# pc_ads1292r_shield_v2.net
KiCad netlist of a schematic drawn in EAGLE
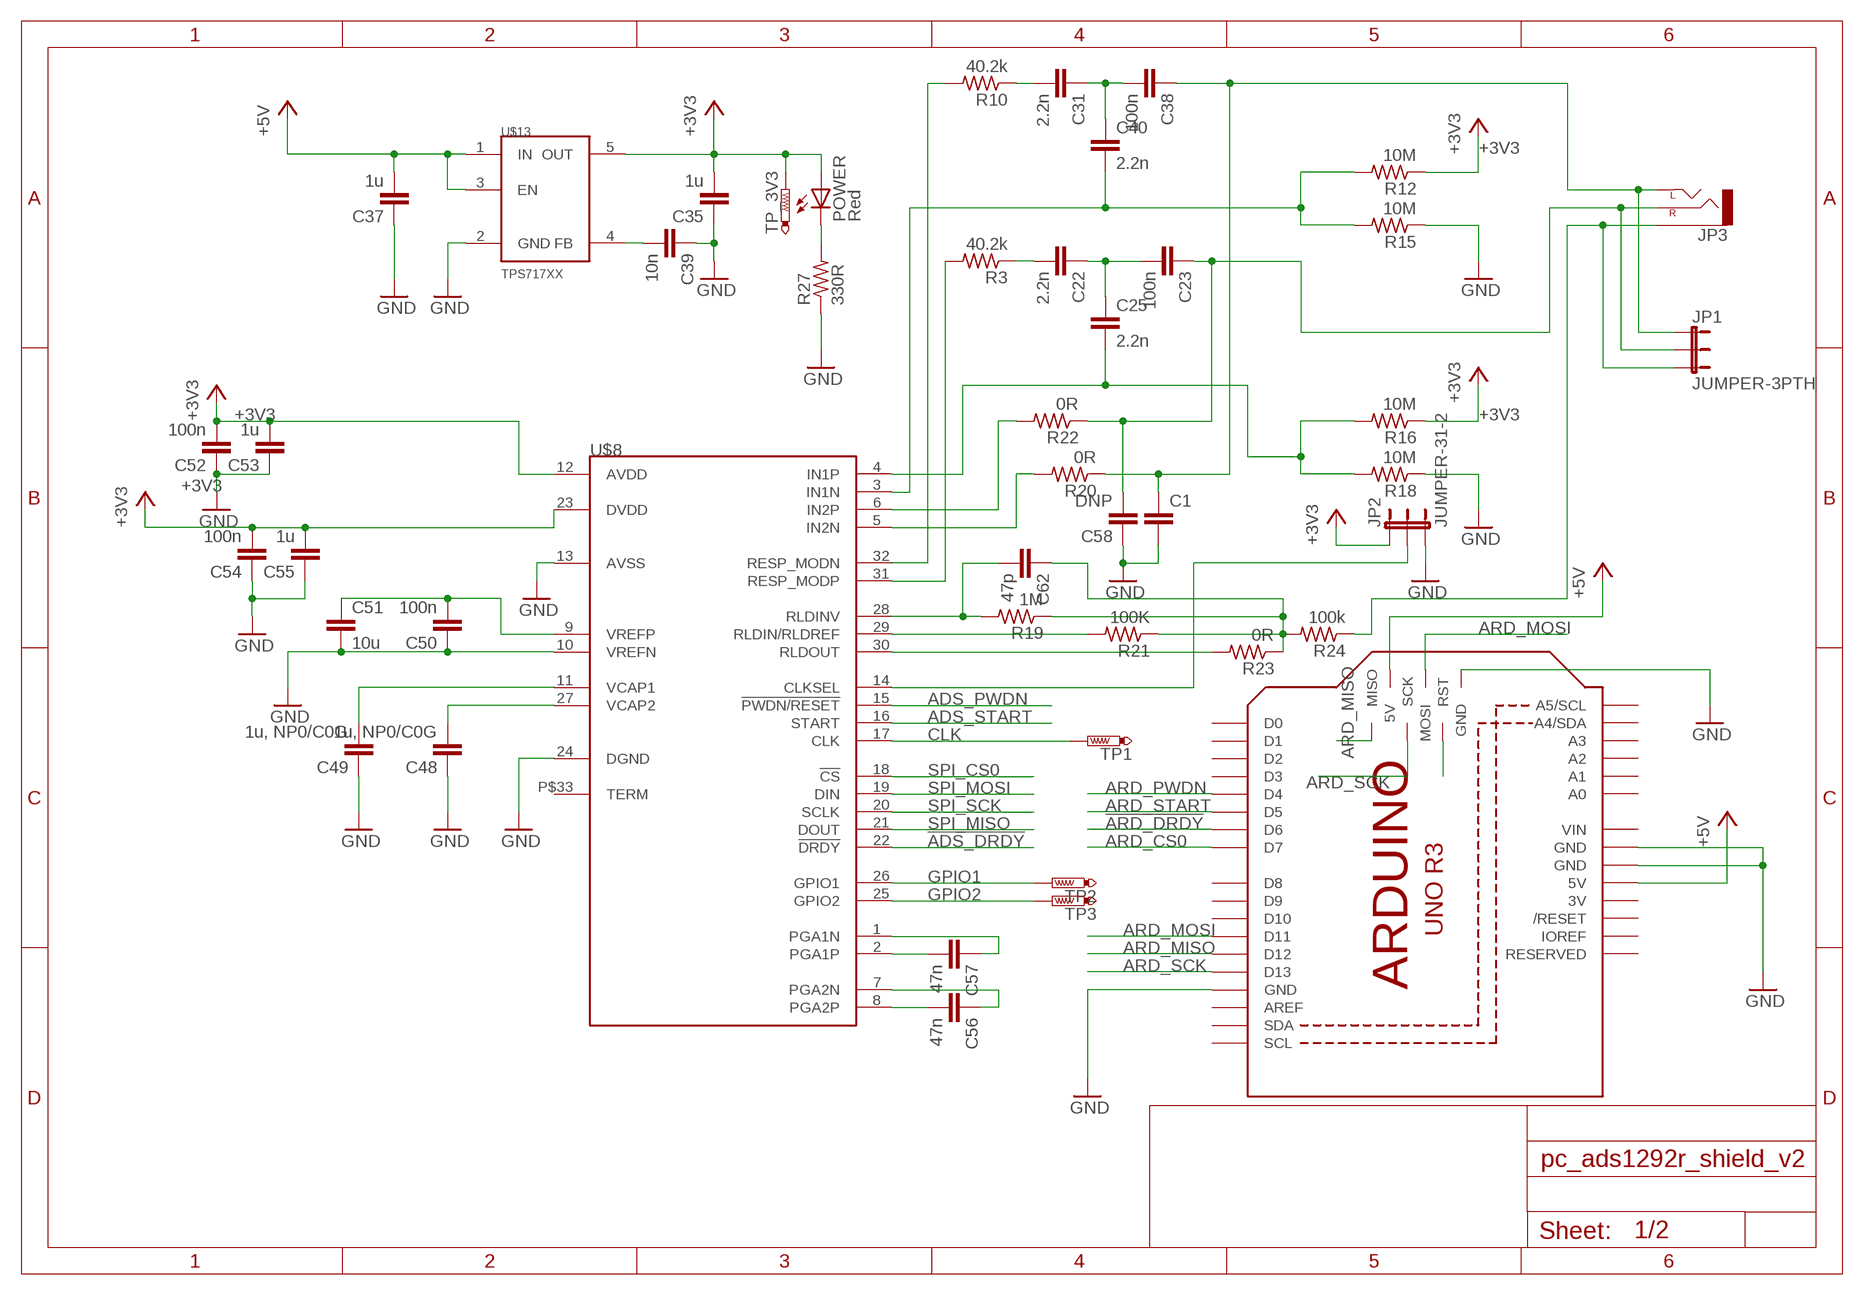
[diagram p0: schematic, sheet 1]
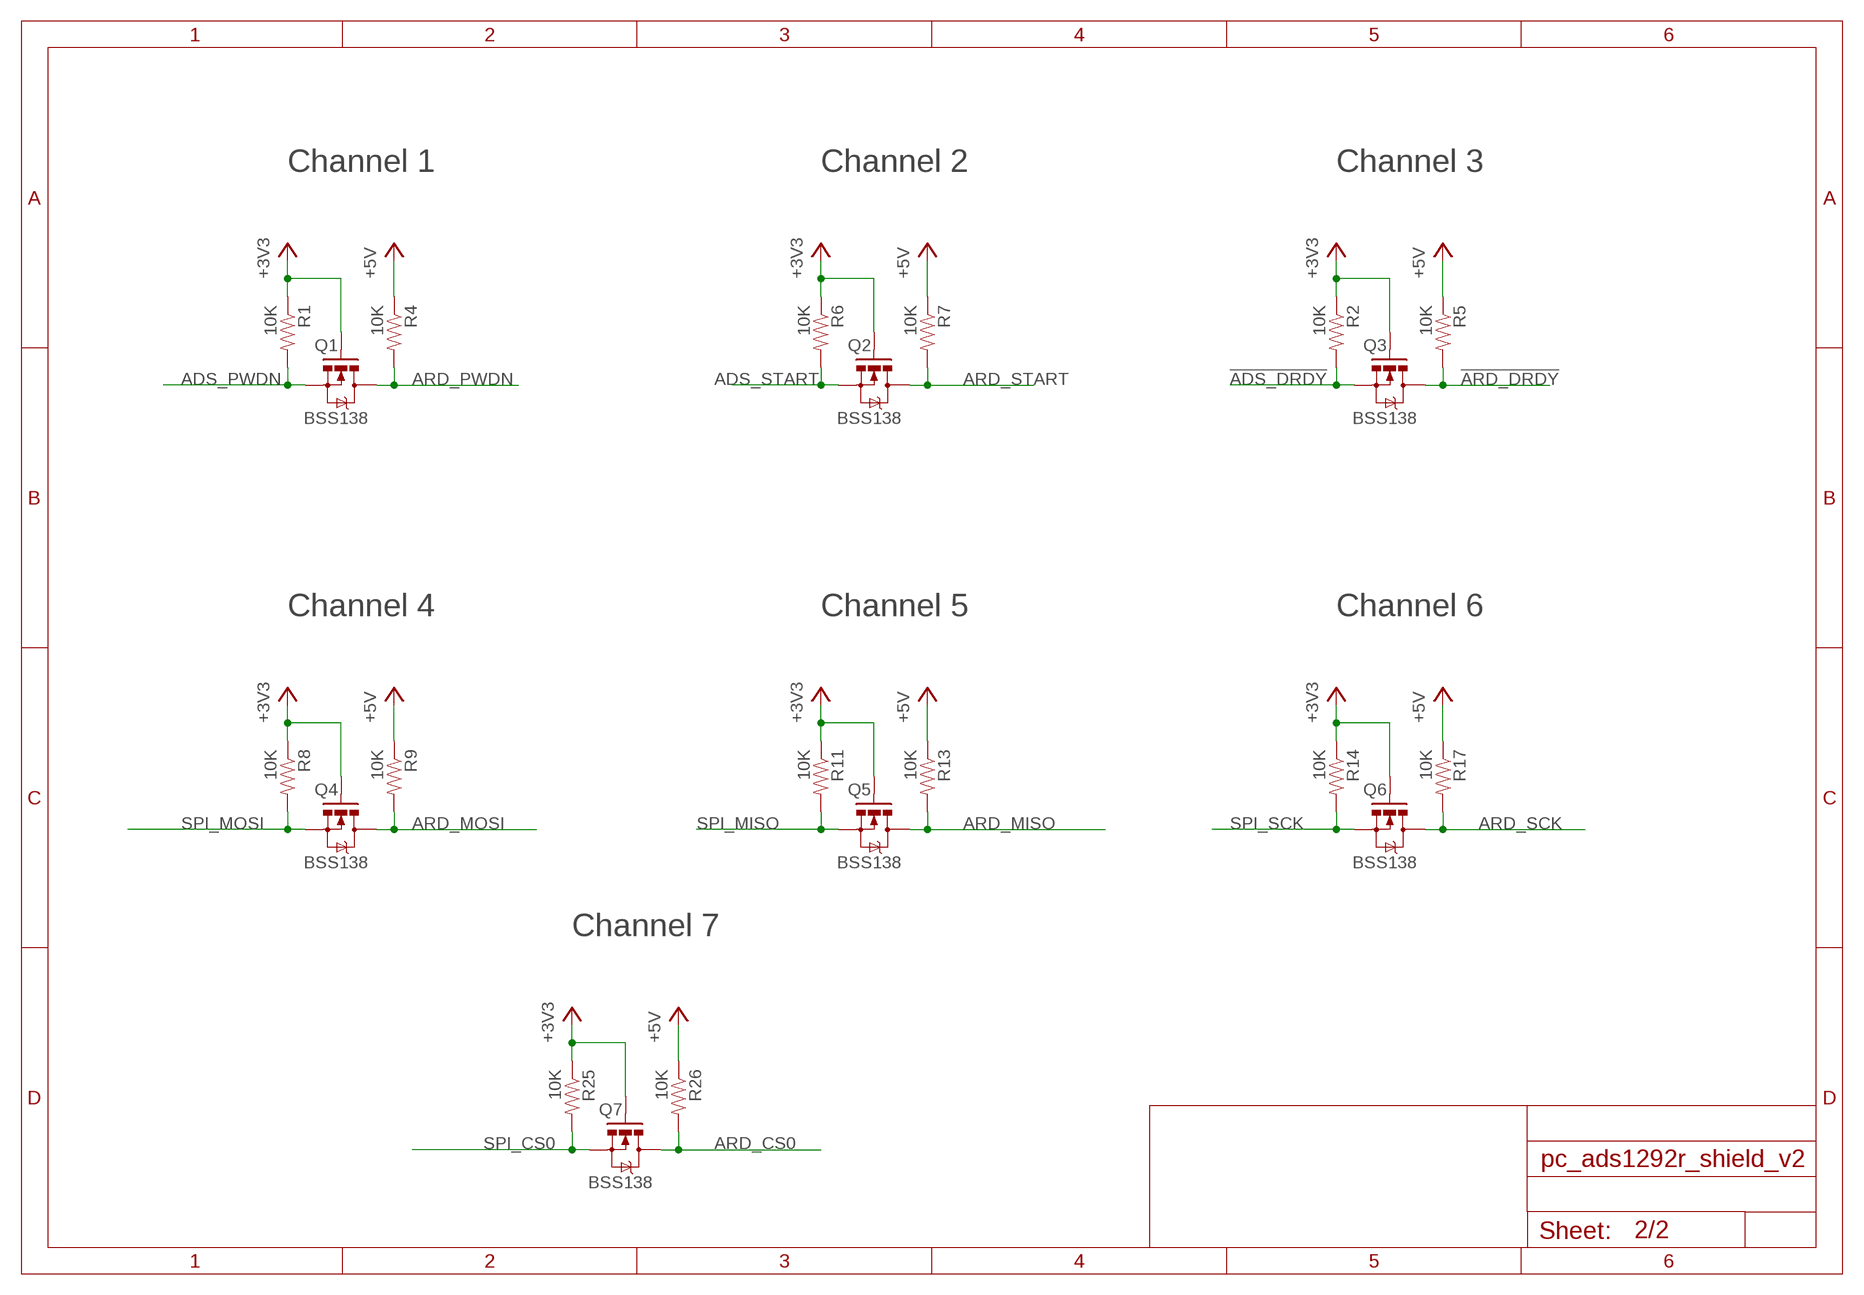
[diagram p1: schematic, sheet 2]

(export (version "E")
  (design (tool "Eeschema 10.0.6"))
  (components
    (comp (ref "C1")
      (value "C-EUC0402")
      (footprint "eagle-import:C0402")
      (libsource (lib "eagle-import") (part "C-EUC0402"))
    )
    (comp (ref "C22")
      (value "2.2n")
      (footprint "eagle-import:C0402")
      (libsource (lib "eagle-import") (part "C-EUC0402"))
    )
    (comp (ref "C23")
      (value "100n")
      (footprint "eagle-import:C0402")
      (libsource (lib "eagle-import") (part "C-EUC0402"))
    )
    (comp (ref "C25")
      (value "2.2n")
      (footprint "eagle-import:C0402")
      (libsource (lib "eagle-import") (part "C-EUC0402"))
    )
    (comp (ref "C31")
      (value "2.2n")
      (footprint "eagle-import:C0402")
      (libsource (lib "eagle-import") (part "C-EUC0402"))
    )
    (comp (ref "C35")
      (value "1u")
      (footprint "eagle-import:C0402")
      (libsource (lib "eagle-import") (part "C-EUC0402"))
    )
    (comp (ref "C37")
      (value "1u")
      (footprint "eagle-import:C0402")
      (libsource (lib "eagle-import") (part "C-EUC0402"))
    )
    (comp (ref "C38")
      (value "100n")
      (footprint "eagle-import:C0402")
      (libsource (lib "eagle-import") (part "C-EUC0402"))
    )
    (comp (ref "C39")
      (value "10n")
      (footprint "eagle-import:C0402")
      (libsource (lib "eagle-import") (part "C-EUC0402"))
    )
    (comp (ref "C40")
      (value "2.2n")
      (footprint "eagle-import:C0402")
      (libsource (lib "eagle-import") (part "C-EUC0402"))
    )
    (comp (ref "C48")
      (value "1u, NP0/C0G")
      (footprint "eagle-import:C0402")
      (libsource (lib "eagle-import") (part "C-EUC0402"))
    )
    (comp (ref "C49")
      (value "1u, NP0/C0G")
      (footprint "eagle-import:C0402")
      (libsource (lib "eagle-import") (part "C-EUC0402"))
    )
    (comp (ref "C50")
      (value "100n")
      (footprint "eagle-import:C0402")
      (libsource (lib "eagle-import") (part "C-EUC0402"))
    )
    (comp (ref "C51")
      (value "10u")
      (footprint "eagle-import:C0603")
      (libsource (lib "eagle-import") (part "resistor_C-EUC0603"))
    )
    (comp (ref "C52")
      (value "100n")
      (footprint "eagle-import:C0402")
      (libsource (lib "eagle-import") (part "C-EUC0402"))
    )
    (comp (ref "C53")
      (value "1u")
      (footprint "eagle-import:C0402")
      (libsource (lib "eagle-import") (part "C-EUC0402"))
    )
    (comp (ref "C54")
      (value "100n")
      (footprint "eagle-import:C0402")
      (libsource (lib "eagle-import") (part "C-EUC0402"))
    )
    (comp (ref "C55")
      (value "1u")
      (footprint "eagle-import:C0402")
      (libsource (lib "eagle-import") (part "C-EUC0402"))
    )
    (comp (ref "C56")
      (value "47n")
      (footprint "eagle-import:C0402")
      (libsource (lib "eagle-import") (part "C-EUC0402"))
    )
    (comp (ref "C57")
      (value "47n")
      (footprint "eagle-import:C0402")
      (libsource (lib "eagle-import") (part "C-EUC0402"))
    )
    (comp (ref "C58")
      (value "DNP")
      (footprint "eagle-import:C0402")
      (libsource (lib "eagle-import") (part "C-EUC0402"))
    )
    (comp (ref "C62")
      (value "47p")
      (footprint "eagle-import:C0402")
      (libsource (lib "eagle-import") (part "C-EUC0402"))
    )
    (comp (ref "JP1")
      (value "JUMPER-3PTH")
      (footprint "eagle-import:1X03")
      (libsource (lib "eagle-import") (part "JUMPER-3PTH"))
    )
    (comp (ref "JP2")
      (value "JUMPER-31-2")
      (footprint "eagle-import:SJ_3_PASTE1&2")
      (libsource (lib "eagle-import") (part "JUMPER-31-2"))
    )
    (comp (ref "JP3")
      (value "AUDIO-JACKSMD2")
      (footprint "eagle-import:AUDIO-JACK-3.5MM-SMD")
      (libsource (lib "eagle-import") (part "AUDIO-JACKSMD2"))
    )
    (comp (ref "M1")
      (value "ARDUINO_R3_ICSP")
      (footprint "eagle-import:ARDUINOR3_ICSP")
      (libsource (lib "eagle-import") (part "ARDUINO_R3_ICSP"))
    )
    (comp (ref "POWER")
      (value "Red")
      (footprint "eagle-import:CHIPLED_0603")
      (libsource (lib "eagle-import") (part "LEDCHIPLED_0603"))
    )
    (comp (ref "R3")
      (value "40.2k")
      (footprint "eagle-import:R0402")
      (libsource (lib "eagle-import") (part "R-US_R0402"))
    )
    (comp (ref "R10")
      (value "40.2k")
      (footprint "eagle-import:R0402")
      (libsource (lib "eagle-import") (part "R-US_R0402"))
    )
    (comp (ref "R12")
      (value "10M")
      (footprint "eagle-import:R0402")
      (libsource (lib "eagle-import") (part "R-US_R0402"))
    )
    (comp (ref "R15")
      (value "10M")
      (footprint "eagle-import:R0402")
      (libsource (lib "eagle-import") (part "R-US_R0402"))
    )
    (comp (ref "R16")
      (value "10M")
      (footprint "eagle-import:R0402")
      (libsource (lib "eagle-import") (part "R-US_R0402"))
    )
    (comp (ref "R18")
      (value "10M")
      (footprint "eagle-import:R0402")
      (libsource (lib "eagle-import") (part "R-US_R0402"))
    )
    (comp (ref "R19")
      (value "1M")
      (footprint "eagle-import:R0402")
      (libsource (lib "eagle-import") (part "R-US_R0402"))
    )
    (comp (ref "R20")
      (value "0R")
      (footprint "eagle-import:R0402")
      (libsource (lib "eagle-import") (part "R-US_R0402"))
    )
    (comp (ref "R21")
      (value "100K")
      (footprint "eagle-import:R0402")
      (libsource (lib "eagle-import") (part "R-US_R0402"))
    )
    (comp (ref "R22")
      (value "0R")
      (footprint "eagle-import:R0402")
      (libsource (lib "eagle-import") (part "R-US_R0402"))
    )
    (comp (ref "R23")
      (value "0R")
      (footprint "eagle-import:R0402")
      (libsource (lib "eagle-import") (part "R-US_R0402"))
    )
    (comp (ref "R24")
      (value "100k")
      (footprint "eagle-import:R0402")
      (libsource (lib "eagle-import") (part "R-US_R0402"))
    )
    (comp (ref "R27")
      (value "330R")
      (footprint "eagle-import:R0402")
      (libsource (lib "eagle-import") (part "R-US_R0402"))
    )
    (comp (ref "TP1")
      (value "PTR1PAD1-17")
      (footprint "eagle-import:P1-17")
      (libsource (lib "eagle-import") (part "PTR1PAD1-17"))
    )
    (comp (ref "TP2")
      (value "PTR1PAD1-17")
      (footprint "eagle-import:P1-17")
      (libsource (lib "eagle-import") (part "PTR1PAD1-17"))
    )
    (comp (ref "TP3")
      (value "PTR1PAD1-17")
      (footprint "eagle-import:P1-17")
      (libsource (lib "eagle-import") (part "PTR1PAD1-17"))
    )
    (comp (ref "TP_3V3")
      (value "PTR1PAD1-13")
      (footprint "eagle-import:P1-13")
      (libsource (lib "eagle-import") (part "PTR1PAD1-13"))
    )
    (comp (ref "U$8")
      (value "ADS1292RPVQFN32")
      (footprint "eagle-import:S-PVQFN-N32")
      (libsource (lib "eagle-import") (part "ADS1292RPVQFN32"))
    )
    (comp (ref "U$13")
      (value "TPS717XX")
      (footprint "eagle-import:SC70-5")
      (libsource (lib "eagle-import") (part "TPS717XX"))
    )
    (comp (ref "Q1")
      (value "BSS138")
      (footprint "eagle-import:SOT23-3")
      (libsource (lib "eagle-import") (part "MOSFET-NCHANNELSMD"))
    )
    (comp (ref "Q2")
      (value "BSS138")
      (footprint "eagle-import:SOT23-3")
      (libsource (lib "eagle-import") (part "MOSFET-NCHANNELSMD"))
    )
    (comp (ref "Q3")
      (value "BSS138")
      (footprint "eagle-import:SOT23-3")
      (libsource (lib "eagle-import") (part "MOSFET-NCHANNELSMD"))
    )
    (comp (ref "Q4")
      (value "BSS138")
      (footprint "eagle-import:SOT23-3")
      (libsource (lib "eagle-import") (part "MOSFET-NCHANNELSMD"))
    )
    (comp (ref "Q5")
      (value "BSS138")
      (footprint "eagle-import:SOT23-3")
      (libsource (lib "eagle-import") (part "MOSFET-NCHANNELSMD"))
    )
    (comp (ref "Q6")
      (value "BSS138")
      (footprint "eagle-import:SOT23-3")
      (libsource (lib "eagle-import") (part "MOSFET-NCHANNELSMD"))
    )
    (comp (ref "Q7")
      (value "BSS138")
      (footprint "eagle-import:SOT23-3")
      (libsource (lib "eagle-import") (part "MOSFET-NCHANNELSMD"))
    )
    (comp (ref "R1")
      (value "10K")
      (footprint "eagle-import:0603-RES")
      (libsource (lib "eagle-import") (part "RESISTOR0603-RES"))
    )
    (comp (ref "R2")
      (value "10K")
      (footprint "eagle-import:0603-RES")
      (libsource (lib "eagle-import") (part "RESISTOR0603-RES"))
    )
    (comp (ref "R4")
      (value "10K")
      (footprint "eagle-import:0603-RES")
      (libsource (lib "eagle-import") (part "RESISTOR0603-RES"))
    )
    (comp (ref "R5")
      (value "10K")
      (footprint "eagle-import:0603-RES")
      (libsource (lib "eagle-import") (part "RESISTOR0603-RES"))
    )
    (comp (ref "R6")
      (value "10K")
      (footprint "eagle-import:0603-RES")
      (libsource (lib "eagle-import") (part "RESISTOR0603-RES"))
    )
    (comp (ref "R7")
      (value "10K")
      (footprint "eagle-import:0603-RES")
      (libsource (lib "eagle-import") (part "RESISTOR0603-RES"))
    )
    (comp (ref "R8")
      (value "10K")
      (footprint "eagle-import:0603-RES")
      (libsource (lib "eagle-import") (part "RESISTOR0603-RES"))
    )
    (comp (ref "R9")
      (value "10K")
      (footprint "eagle-import:0603-RES")
      (libsource (lib "eagle-import") (part "RESISTOR0603-RES"))
    )
    (comp (ref "R11")
      (value "10K")
      (footprint "eagle-import:0603-RES")
      (libsource (lib "eagle-import") (part "RESISTOR0603-RES"))
    )
    (comp (ref "R13")
      (value "10K")
      (footprint "eagle-import:0603-RES")
      (libsource (lib "eagle-import") (part "RESISTOR0603-RES"))
    )
    (comp (ref "R14")
      (value "10K")
      (footprint "eagle-import:0603-RES")
      (libsource (lib "eagle-import") (part "RESISTOR0603-RES"))
    )
    (comp (ref "R17")
      (value "10K")
      (footprint "eagle-import:0603-RES")
      (libsource (lib "eagle-import") (part "RESISTOR0603-RES"))
    )
    (comp (ref "R25")
      (value "10K")
      (footprint "eagle-import:0603-RES")
      (libsource (lib "eagle-import") (part "RESISTOR0603-RES"))
    )
    (comp (ref "R26")
      (value "10K")
      (footprint "eagle-import:0603-RES")
      (libsource (lib "eagle-import") (part "RESISTOR0603-RES"))
    )
  )
  (nets
    (net (code "1") (name "+3V3") (class "Default")
      (node (ref "C35") (pin "2") (pinfunction "2_2") (pintype "passive"))
      (node (ref "C52") (pin "2") (pinfunction "2_2") (pintype "passive"))
      (node (ref "C53") (pin "2") (pinfunction "2_2") (pintype "passive"))
      (node (ref "C54") (pin "2") (pinfunction "2_2") (pintype "passive"))
      (node (ref "C55") (pin "2") (pinfunction "2_2") (pintype "passive"))
      (node (ref "JP2") (pin "1") (pinfunction "1_1") (pintype "passive"))
      (node (ref "POWER") (pin "A") (pinfunction "A_A") (pintype "passive"))
      (node (ref "Q1") (pin "1") (pinfunction "G_1") (pintype "passive"))
      (node (ref "Q2") (pin "1") (pinfunction "G_1") (pintype "passive"))
      (node (ref "Q3") (pin "1") (pinfunction "G_1") (pintype "passive"))
      (node (ref "Q4") (pin "1") (pinfunction "G_1") (pintype "passive"))
      (node (ref "Q5") (pin "1") (pinfunction "G_1") (pintype "passive"))
      (node (ref "Q6") (pin "1") (pinfunction "G_1") (pintype "passive"))
      (node (ref "Q7") (pin "1") (pinfunction "G_1") (pintype "passive"))
      (node (ref "R1") (pin "1") (pinfunction "1_1") (pintype "passive"))
      (node (ref "R11") (pin "1") (pinfunction "1_1") (pintype "passive"))
      (node (ref "R12") (pin "1") (pinfunction "1_1") (pintype "passive"))
      (node (ref "R14") (pin "1") (pinfunction "1_1") (pintype "passive"))
      (node (ref "R16") (pin "1") (pinfunction "1_1") (pintype "passive"))
      (node (ref "R2") (pin "1") (pinfunction "1_1") (pintype "passive"))
      (node (ref "R25") (pin "1") (pinfunction "1_1") (pintype "passive"))
      (node (ref "R6") (pin "1") (pinfunction "1_1") (pintype "passive"))
      (node (ref "R8") (pin "1") (pinfunction "1_1") (pintype "passive"))
      (node (ref "TP_3V3") (pin "TP") (pinfunction "TP_TP") (pintype "input"))
      (node (ref "U$13") (pin "5") (pinfunction "OUT_5") (pintype "bidirectional"))
      (node (ref "U$8") (pin "12") (pinfunction "AVDD_12") (pintype "power_in"))
      (node (ref "U$8") (pin "23") (pinfunction "DVDD_23") (pintype "power_in"))
    )
    (net (code "2") (name "+5V") (class "Default")
      (node (ref "C37") (pin "2") (pinfunction "2_2") (pintype "passive"))
      (node (ref "M1") (pin "5V") (pinfunction "5V_5V") (pintype "power_in"))
      (node (ref "M1") (pin "5V_ICSP") (pinfunction "5V_5V_ICSP") (pintype "passive"))
      (node (ref "R13") (pin "1") (pinfunction "1_1") (pintype "passive"))
      (node (ref "R17") (pin "1") (pinfunction "1_1") (pintype "passive"))
      (node (ref "R26") (pin "1") (pinfunction "1_1") (pintype "passive"))
      (node (ref "R4") (pin "1") (pinfunction "1_1") (pintype "passive"))
      (node (ref "R5") (pin "1") (pinfunction "1_1") (pintype "passive"))
      (node (ref "R7") (pin "1") (pinfunction "1_1") (pintype "passive"))
      (node (ref "R9") (pin "1") (pinfunction "1_1") (pintype "passive"))
      (node (ref "U$13") (pin "1") (pinfunction "IN_1") (pintype "bidirectional"))
      (node (ref "U$13") (pin "3") (pinfunction "EN_3") (pintype "bidirectional"))
    )
    (net (code "3") (name "3V") (class "Default")
      (node (ref "M1") (pin "3V") (pinfunction "3V_3V") (pintype "power_in"))
    )
    (net (code "4") (name "ADS_PWDN") (class "Default")
      (node (ref "Q1") (pin "2") (pinfunction "S_2") (pintype "passive"))
      (node (ref "R1") (pin "2") (pinfunction "2_2") (pintype "passive"))
      (node (ref "U$8") (pin "15") (pinfunction "~{PWDN/RESET}_15") (pintype "bidirectional"))
    )
    (net (code "5") (name "ADS_START") (class "Default")
      (node (ref "Q2") (pin "2") (pinfunction "S_2") (pintype "passive"))
      (node (ref "R6") (pin "2") (pinfunction "2_2") (pintype "passive"))
      (node (ref "U$8") (pin "16") (pinfunction "START_16") (pintype "bidirectional"))
    )
    (net (code "6") (name "ARD_CS0") (class "Default")
      (node (ref "M1") (pin "D7") (pinfunction "D7_D7") (pintype "bidirectional"))
      (node (ref "Q7") (pin "3") (pinfunction "D_3") (pintype "passive"))
      (node (ref "R26") (pin "2") (pinfunction "2_2") (pintype "passive"))
    )
    (net (code "7") (name "ARD_MISO") (class "Default")
      (node (ref "M1") (pin "D12") (pinfunction "D12_D12") (pintype "bidirectional"))
      (node (ref "M1") (pin "MISO") (pinfunction "MISO_MISO") (pintype "passive"))
      (node (ref "Q5") (pin "3") (pinfunction "D_3") (pintype "passive"))
      (node (ref "R13") (pin "2") (pinfunction "2_2") (pintype "passive"))
    )
    (net (code "8") (name "ARD_MOSI") (class "Default")
      (node (ref "M1") (pin "D11") (pinfunction "D11_D11") (pintype "bidirectional"))
      (node (ref "M1") (pin "MOSI") (pinfunction "MOSI_MOSI") (pintype "passive"))
      (node (ref "Q4") (pin "3") (pinfunction "D_3") (pintype "passive"))
      (node (ref "R9") (pin "2") (pinfunction "2_2") (pintype "passive"))
    )
    (net (code "9") (name "ARD_PWDN") (class "Default")
      (node (ref "M1") (pin "D4") (pinfunction "D4_D4") (pintype "bidirectional"))
      (node (ref "Q1") (pin "3") (pinfunction "D_3") (pintype "passive"))
      (node (ref "R4") (pin "2") (pinfunction "2_2") (pintype "passive"))
    )
    (net (code "10") (name "ARD_SCK") (class "Default")
      (node (ref "M1") (pin "D13") (pinfunction "D13_D13") (pintype "bidirectional"))
      (node (ref "M1") (pin "SCK") (pinfunction "SCK_SCK") (pintype "passive"))
      (node (ref "Q6") (pin "3") (pinfunction "D_3") (pintype "passive"))
      (node (ref "R17") (pin "2") (pinfunction "2_2") (pintype "passive"))
    )
    (net (code "11") (name "ARD_START") (class "Default")
      (node (ref "M1") (pin "D5") (pinfunction "D5_D5") (pintype "bidirectional"))
      (node (ref "Q2") (pin "3") (pinfunction "D_3") (pintype "passive"))
      (node (ref "R7") (pin "2") (pinfunction "2_2") (pintype "passive"))
    )
    (net (code "12") (name "CLK") (class "Default")
      (node (ref "TP1") (pin "TP") (pinfunction "TP_TP") (pintype "input"))
      (node (ref "U$8") (pin "17") (pinfunction "CLK_17") (pintype "bidirectional"))
    )
    (net (code "13") (name "GND") (class "Default")
      (node (ref "C1") (pin "2") (pinfunction "2_2") (pintype "passive"))
      (node (ref "C35") (pin "1") (pinfunction "1_1") (pintype "passive"))
      (node (ref "C37") (pin "1") (pinfunction "1_1") (pintype "passive"))
      (node (ref "C39") (pin "1") (pinfunction "1_1") (pintype "passive"))
      (node (ref "C48") (pin "1") (pinfunction "1_1") (pintype "passive"))
      (node (ref "C49") (pin "1") (pinfunction "1_1") (pintype "passive"))
      (node (ref "C50") (pin "1") (pinfunction "1_1") (pintype "passive"))
      (node (ref "C51") (pin "2") (pinfunction "2_2") (pintype "passive"))
      (node (ref "C52") (pin "1") (pinfunction "1_1") (pintype "passive"))
      (node (ref "C53") (pin "1") (pinfunction "1_1") (pintype "passive"))
      (node (ref "C54") (pin "1") (pinfunction "1_1") (pintype "passive"))
      (node (ref "C55") (pin "1") (pinfunction "1_1") (pintype "passive"))
      (node (ref "C58") (pin "1") (pinfunction "1_1") (pintype "passive"))
      (node (ref "JP2") (pin "3") (pinfunction "3_3") (pintype "passive"))
      (node (ref "M1") (pin "GND") (pinfunction "GND_GND") (pintype "power_in"))
      (node (ref "M1") (pin "GND@1") (pinfunction "GND_GND@1") (pintype "power_in"))
      (node (ref "M1") (pin "GND@2") (pinfunction "GND_GND@2") (pintype "passive"))
      (node (ref "M1") (pin "GND@3") (pinfunction "GND_GND@3") (pintype "power_in"))
      (node (ref "R15") (pin "1") (pinfunction "1_1") (pintype "passive"))
      (node (ref "R18") (pin "1") (pinfunction "1_1") (pintype "passive"))
      (node (ref "R27") (pin "1") (pinfunction "1_1") (pintype "passive"))
      (node (ref "U$13") (pin "2") (pinfunction "GND_2") (pintype "bidirectional"))
      (node (ref "U$8") (pin "10") (pinfunction "VREFN_10") (pintype "bidirectional"))
      (node (ref "U$8") (pin "13") (pinfunction "AVSS_13") (pintype "bidirectional"))
      (node (ref "U$8") (pin "24") (pinfunction "DGND_24") (pintype "bidirectional"))
    )
    (net (code "14") (name "GPIO1") (class "Default")
      (node (ref "TP2") (pin "TP") (pinfunction "TP_TP") (pintype "input"))
      (node (ref "U$8") (pin "26") (pinfunction "GPIO1_26") (pintype "bidirectional"))
    )
    (net (code "15") (name "GPIO2") (class "Default")
      (node (ref "TP3") (pin "TP") (pinfunction "TP_TP") (pintype "input"))
      (node (ref "U$8") (pin "25") (pinfunction "GPIO2_25") (pintype "bidirectional"))
    )
    (net (code "16") (name "Net-(C22-Pad1)") (class "Default")
      (node (ref "C22") (pin "1") (pinfunction "1_1") (pintype "passive"))
      (node (ref "C23") (pin "2") (pinfunction "2_2") (pintype "passive"))
      (node (ref "C25") (pin "1") (pinfunction "1_1") (pintype "passive"))
    )
    (net (code "17") (name "Net-(C22-Pad2)") (class "Default")
      (node (ref "C22") (pin "2") (pinfunction "2_2") (pintype "passive"))
      (node (ref "R3") (pin "1") (pinfunction "1_1") (pintype "passive"))
    )
    (net (code "18") (name "Net-(C31-Pad1)") (class "Default")
      (node (ref "C31") (pin "1") (pinfunction "1_1") (pintype "passive"))
      (node (ref "C38") (pin "2") (pinfunction "2_2") (pintype "passive"))
      (node (ref "C40") (pin "1") (pinfunction "1_1") (pintype "passive"))
    )
    (net (code "19") (name "Net-(C31-Pad2)") (class "Default")
      (node (ref "C31") (pin "2") (pinfunction "2_2") (pintype "passive"))
      (node (ref "R10") (pin "1") (pinfunction "1_1") (pintype "passive"))
    )
    (net (code "20") (name "Net-(C62-Pad1)") (class "Default")
      (node (ref "C62") (pin "1") (pinfunction "1_1") (pintype "passive"))
      (node (ref "R19") (pin "1") (pinfunction "1_1") (pintype "passive"))
      (node (ref "R21") (pin "1") (pinfunction "1_1") (pintype "passive"))
      (node (ref "R23") (pin "1") (pinfunction "1_1") (pintype "passive"))
      (node (ref "R24") (pin "2") (pinfunction "2_2") (pintype "passive"))
    )
    (net (code "21") (name "Net-(JP1-Pad3)") (class "Default")
      (node (ref "JP1") (pin "3") (pinfunction "3_3") (pintype "passive"))
      (node (ref "JP3") (pin "SLEEVE") (pinfunction "SLEEVE_SLEEVE") (pintype "bidirectional"))
      (node (ref "R24") (pin "1") (pinfunction "1_1") (pintype "passive"))
    )
    (net (code "22") (name "Net-(JP3-LEFT)") (class "Default")
      (node (ref "C1") (pin "1") (pinfunction "1_1") (pintype "passive"))
      (node (ref "C38") (pin "1") (pinfunction "1_1") (pintype "passive"))
      (node (ref "JP1") (pin "1") (pinfunction "1_1") (pintype "passive"))
      (node (ref "JP3") (pin "TIP") (pinfunction "LEFT_TIP") (pintype "bidirectional"))
      (node (ref "R20") (pin "1") (pinfunction "1_1") (pintype "passive"))
    )
    (net (code "23") (name "Net-(JP3-RIGHT)") (class "Default")
      (node (ref "C23") (pin "1") (pinfunction "1_1") (pintype "passive"))
      (node (ref "C58") (pin "2") (pinfunction "2_2") (pintype "passive"))
      (node (ref "JP1") (pin "2") (pinfunction "2_2") (pintype "passive"))
      (node (ref "JP3") (pin "RING") (pinfunction "RIGHT_RING") (pintype "bidirectional"))
      (node (ref "R22") (pin "1") (pinfunction "1_1") (pintype "passive"))
    )
    (net (code "24") (name "Net-(POWER-PadC)") (class "Default")
      (node (ref "POWER") (pin "C") (pinfunction "C_C") (pintype "passive"))
      (node (ref "R27") (pin "2") (pinfunction "2_2") (pintype "passive"))
    )
    (net (code "25") (name "Net-(U$8-CLKSEL)") (class "Default")
      (node (ref "JP2") (pin "2") (pinfunction "2_2") (pintype "passive"))
      (node (ref "U$8") (pin "14") (pinfunction "CLKSEL_14") (pintype "bidirectional"))
    )
    (net (code "26") (name "Net-(U$8-IN1N)") (class "Default")
      (node (ref "C40") (pin "2") (pinfunction "2_2") (pintype "passive"))
      (node (ref "R12") (pin "2") (pinfunction "2_2") (pintype "passive"))
      (node (ref "R15") (pin "2") (pinfunction "2_2") (pintype "passive"))
      (node (ref "U$8") (pin "3") (pinfunction "IN1N_3") (pintype "input"))
    )
    (net (code "27") (name "Net-(U$8-IN1P)") (class "Default")
      (node (ref "C25") (pin "2") (pinfunction "2_2") (pintype "passive"))
      (node (ref "R16") (pin "2") (pinfunction "2_2") (pintype "passive"))
      (node (ref "R18") (pin "2") (pinfunction "2_2") (pintype "passive"))
      (node (ref "U$8") (pin "4") (pinfunction "IN1P_4") (pintype "input"))
    )
    (net (code "28") (name "Net-(U$8-IN2N)") (class "Default")
      (node (ref "R20") (pin "2") (pinfunction "2_2") (pintype "passive"))
      (node (ref "U$8") (pin "5") (pinfunction "IN2N_5") (pintype "input"))
    )
    (net (code "29") (name "Net-(U$8-IN2P)") (class "Default")
      (node (ref "R22") (pin "2") (pinfunction "2_2") (pintype "passive"))
      (node (ref "U$8") (pin "6") (pinfunction "IN2P_6") (pintype "input"))
    )
    (net (code "30") (name "Net-(U$8-PGA1N)") (class "Default")
      (node (ref "C57") (pin "1") (pinfunction "1_1") (pintype "passive"))
      (node (ref "U$8") (pin "1") (pinfunction "PGA1N_1") (pintype "bidirectional"))
    )
    (net (code "31") (name "Net-(U$8-PGA1P)") (class "Default")
      (node (ref "C57") (pin "2") (pinfunction "2_2") (pintype "passive"))
      (node (ref "U$8") (pin "2") (pinfunction "PGA1P_2") (pintype "bidirectional"))
    )
    (net (code "32") (name "Net-(U$8-PGA2N)") (class "Default")
      (node (ref "C56") (pin "1") (pinfunction "1_1") (pintype "passive"))
      (node (ref "U$8") (pin "7") (pinfunction "PGA2N_7") (pintype "bidirectional"))
    )
    (net (code "33") (name "Net-(U$8-PGA2P)") (class "Default")
      (node (ref "C56") (pin "2") (pinfunction "2_2") (pintype "passive"))
      (node (ref "U$8") (pin "8") (pinfunction "PGA2P_8") (pintype "bidirectional"))
    )
    (net (code "34") (name "Net-(U$8-RESP_MODN)") (class "Default")
      (node (ref "R10") (pin "2") (pinfunction "2_2") (pintype "passive"))
      (node (ref "U$8") (pin "32") (pinfunction "RESP_MODN_32") (pintype "bidirectional"))
    )
    (net (code "35") (name "Net-(U$8-RESP_MODP)") (class "Default")
      (node (ref "R3") (pin "2") (pinfunction "2_2") (pintype "passive"))
      (node (ref "U$8") (pin "31") (pinfunction "RESP_MODP_31") (pintype "bidirectional"))
    )
    (net (code "36") (name "Net-(U$8-RLDINV)") (class "Default")
      (node (ref "C62") (pin "2") (pinfunction "2_2") (pintype "passive"))
      (node (ref "R19") (pin "2") (pinfunction "2_2") (pintype "passive"))
      (node (ref "U$8") (pin "28") (pinfunction "RLDINV_28") (pintype "bidirectional"))
    )
    (net (code "37") (name "Net-(U$8-RLDIN{slash}RLDREF)") (class "Default")
      (node (ref "R21") (pin "2") (pinfunction "2_2") (pintype "passive"))
      (node (ref "U$8") (pin "29") (pinfunction "RLDIN/RLDREF_29") (pintype "bidirectional"))
    )
    (net (code "38") (name "Net-(U$8-RLDOUT)") (class "Default")
      (node (ref "R23") (pin "2") (pinfunction "2_2") (pintype "passive"))
      (node (ref "U$8") (pin "30") (pinfunction "RLDOUT_30") (pintype "bidirectional"))
    )
    (net (code "39") (name "Net-(U$8-VCAP1)") (class "Default")
      (node (ref "C49") (pin "2") (pinfunction "2_2") (pintype "passive"))
      (node (ref "U$8") (pin "11") (pinfunction "VCAP1_11") (pintype "bidirectional"))
    )
    (net (code "40") (name "Net-(U$8-VCAP2)") (class "Default")
      (node (ref "C48") (pin "2") (pinfunction "2_2") (pintype "passive"))
      (node (ref "U$8") (pin "27") (pinfunction "VCAP2_27") (pintype "bidirectional"))
    )
    (net (code "41") (name "Net-(U$8-VREFP)") (class "Default")
      (node (ref "C50") (pin "2") (pinfunction "2_2") (pintype "passive"))
      (node (ref "C51") (pin "1") (pinfunction "1_1") (pintype "passive"))
      (node (ref "U$8") (pin "9") (pinfunction "VREFP_9") (pintype "bidirectional"))
    )
    (net (code "42") (name "Net-(U$13-FB)") (class "Default")
      (node (ref "C39") (pin "2") (pinfunction "2_2") (pintype "passive"))
      (node (ref "U$13") (pin "4") (pinfunction "FB_4") (pintype "bidirectional"))
    )
    (net (code "43") (name "SPI_CS0") (class "Default")
      (node (ref "Q7") (pin "2") (pinfunction "S_2") (pintype "passive"))
      (node (ref "R25") (pin "2") (pinfunction "2_2") (pintype "passive"))
      (node (ref "U$8") (pin "18") (pinfunction "~{CS}_18") (pintype "bidirectional"))
    )
    (net (code "44") (name "SPI_MISO") (class "Default")
      (node (ref "Q5") (pin "2") (pinfunction "S_2") (pintype "passive"))
      (node (ref "R11") (pin "2") (pinfunction "2_2") (pintype "passive"))
      (node (ref "U$8") (pin "21") (pinfunction "DOUT_21") (pintype "bidirectional"))
    )
    (net (code "45") (name "SPI_MOSI") (class "Default")
      (node (ref "Q4") (pin "2") (pinfunction "S_2") (pintype "passive"))
      (node (ref "R8") (pin "2") (pinfunction "2_2") (pintype "passive"))
      (node (ref "U$8") (pin "19") (pinfunction "DIN_19") (pintype "bidirectional"))
    )
    (net (code "46") (name "SPI_SCK") (class "Default")
      (node (ref "Q6") (pin "2") (pinfunction "S_2") (pintype "passive"))
      (node (ref "R14") (pin "2") (pinfunction "2_2") (pintype "passive"))
      (node (ref "U$8") (pin "20") (pinfunction "SCLK_20") (pintype "bidirectional"))
    )
    (net (code "47") (name "VIN") (class "Default")
      (node (ref "M1") (pin "VIN") (pinfunction "VIN_VIN") (pintype "power_in"))
    )
    (net (code "48") (name "unconnected-(M1-A4{slash}SDA-PadA4)") (class "Default")
      (node (ref "M1") (pin "A4") (pinfunction "A4/SDA_A4") (pintype "bidirectional"))
    )
    (net (code "49") (name "unconnected-(M1-A5{slash}SCL-PadA5)") (class "Default")
      (node (ref "M1") (pin "A5") (pinfunction "A5/SCL_A5") (pintype "bidirectional"))
    )
    (net (code "50") (name "unconnected-(M1-PadA0)") (class "Default")
      (node (ref "M1") (pin "A0") (pinfunction "A0_A0") (pintype "bidirectional"))
    )
    (net (code "51") (name "unconnected-(M1-PadA1)") (class "Default")
      (node (ref "M1") (pin "A1") (pinfunction "A1_A1") (pintype "bidirectional"))
    )
    (net (code "52") (name "unconnected-(M1-PadA2)") (class "Default")
      (node (ref "M1") (pin "A2") (pinfunction "A2_A2") (pintype "bidirectional"))
    )
    (net (code "53") (name "unconnected-(M1-PadA3)") (class "Default")
      (node (ref "M1") (pin "A3") (pinfunction "A3_A3") (pintype "bidirectional"))
    )
    (net (code "54") (name "unconnected-(M1-PadAREF)") (class "Default")
      (node (ref "M1") (pin "AREF") (pinfunction "AREF_AREF") (pintype "bidirectional"))
    )
    (net (code "55") (name "unconnected-(M1-PadD0)") (class "Default")
      (node (ref "M1") (pin "D0") (pinfunction "D0_D0") (pintype "bidirectional"))
    )
    (net (code "56") (name "unconnected-(M1-PadD1)") (class "Default")
      (node (ref "M1") (pin "D1") (pinfunction "D1_D1") (pintype "bidirectional"))
    )
    (net (code "57") (name "unconnected-(M1-PadD2)") (class "Default")
      (node (ref "M1") (pin "D2") (pinfunction "D2_D2") (pintype "bidirectional"))
    )
    (net (code "58") (name "unconnected-(M1-PadD3)") (class "Default")
      (node (ref "M1") (pin "D3") (pinfunction "D3_D3") (pintype "bidirectional"))
    )
    (net (code "59") (name "unconnected-(M1-PadD8)") (class "Default")
      (node (ref "M1") (pin "D8") (pinfunction "D8_D8") (pintype "bidirectional"))
    )
    (net (code "60") (name "unconnected-(M1-PadD9)") (class "Default")
      (node (ref "M1") (pin "D9") (pinfunction "D9_D9") (pintype "bidirectional"))
    )
    (net (code "61") (name "unconnected-(M1-PadD10)") (class "Default")
      (node (ref "M1") (pin "D10") (pinfunction "D10_D10") (pintype "bidirectional"))
    )
    (net (code "62") (name "unconnected-(M1-PadIOREF)") (class "Default")
      (node (ref "M1") (pin "IOREF") (pinfunction "IOREF_IOREF") (pintype "output"))
    )
    (net (code "63") (name "unconnected-(M1-PadRESERVED)") (class "Default")
      (node (ref "M1") (pin "RESERVED") (pinfunction "RESERVED_RESERVED") (pintype "no_connect"))
    )
    (net (code "64") (name "unconnected-(M1-PadSCL)") (class "Default")
      (node (ref "M1") (pin "SCL") (pinfunction "SCL_SCL") (pintype "bidirectional"))
    )
    (net (code "65") (name "unconnected-(M1-PadSDA)") (class "Default")
      (node (ref "M1") (pin "SDA") (pinfunction "SDA_SDA") (pintype "bidirectional"))
    )
    (net (code "66") (name "unconnected-(M1-RST-PadRESET_ICSP)") (class "Default")
      (node (ref "M1") (pin "RESET_ICSP") (pinfunction "RST_RESET_ICSP") (pintype "passive"))
    )
    (net (code "67") (name "unconnected-(M1-{slash}RESET-PadRESET)") (class "Default")
      (node (ref "M1") (pin "RESET") (pinfunction "/RESET_RESET") (pintype "bidirectional"))
    )
    (net (code "68") (name "unconnected-(U$8-TERM-PadP$33)") (class "Default")
      (node (ref "U$8") (pin "P$33") (pinfunction "TERM_P$33") (pintype "bidirectional"))
    )
    (net (code "69") (name "~{ADS_DRDY}") (class "Default")
      (node (ref "Q3") (pin "2") (pinfunction "S_2") (pintype "passive"))
      (node (ref "R2") (pin "2") (pinfunction "2_2") (pintype "passive"))
      (node (ref "U$8") (pin "22") (pinfunction "~{DRDY}_22") (pintype "bidirectional"))
    )
    (net (code "70") (name "~{ARD_DRDY}") (class "Default")
      (node (ref "M1") (pin "D6") (pinfunction "D6_D6") (pintype "bidirectional"))
      (node (ref "Q3") (pin "3") (pinfunction "D_3") (pintype "passive"))
      (node (ref "R5") (pin "2") (pinfunction "2_2") (pintype "passive"))
    )
  )
)
